# prototype2.net
KiCad netlist of a schematic drawn in EAGLE
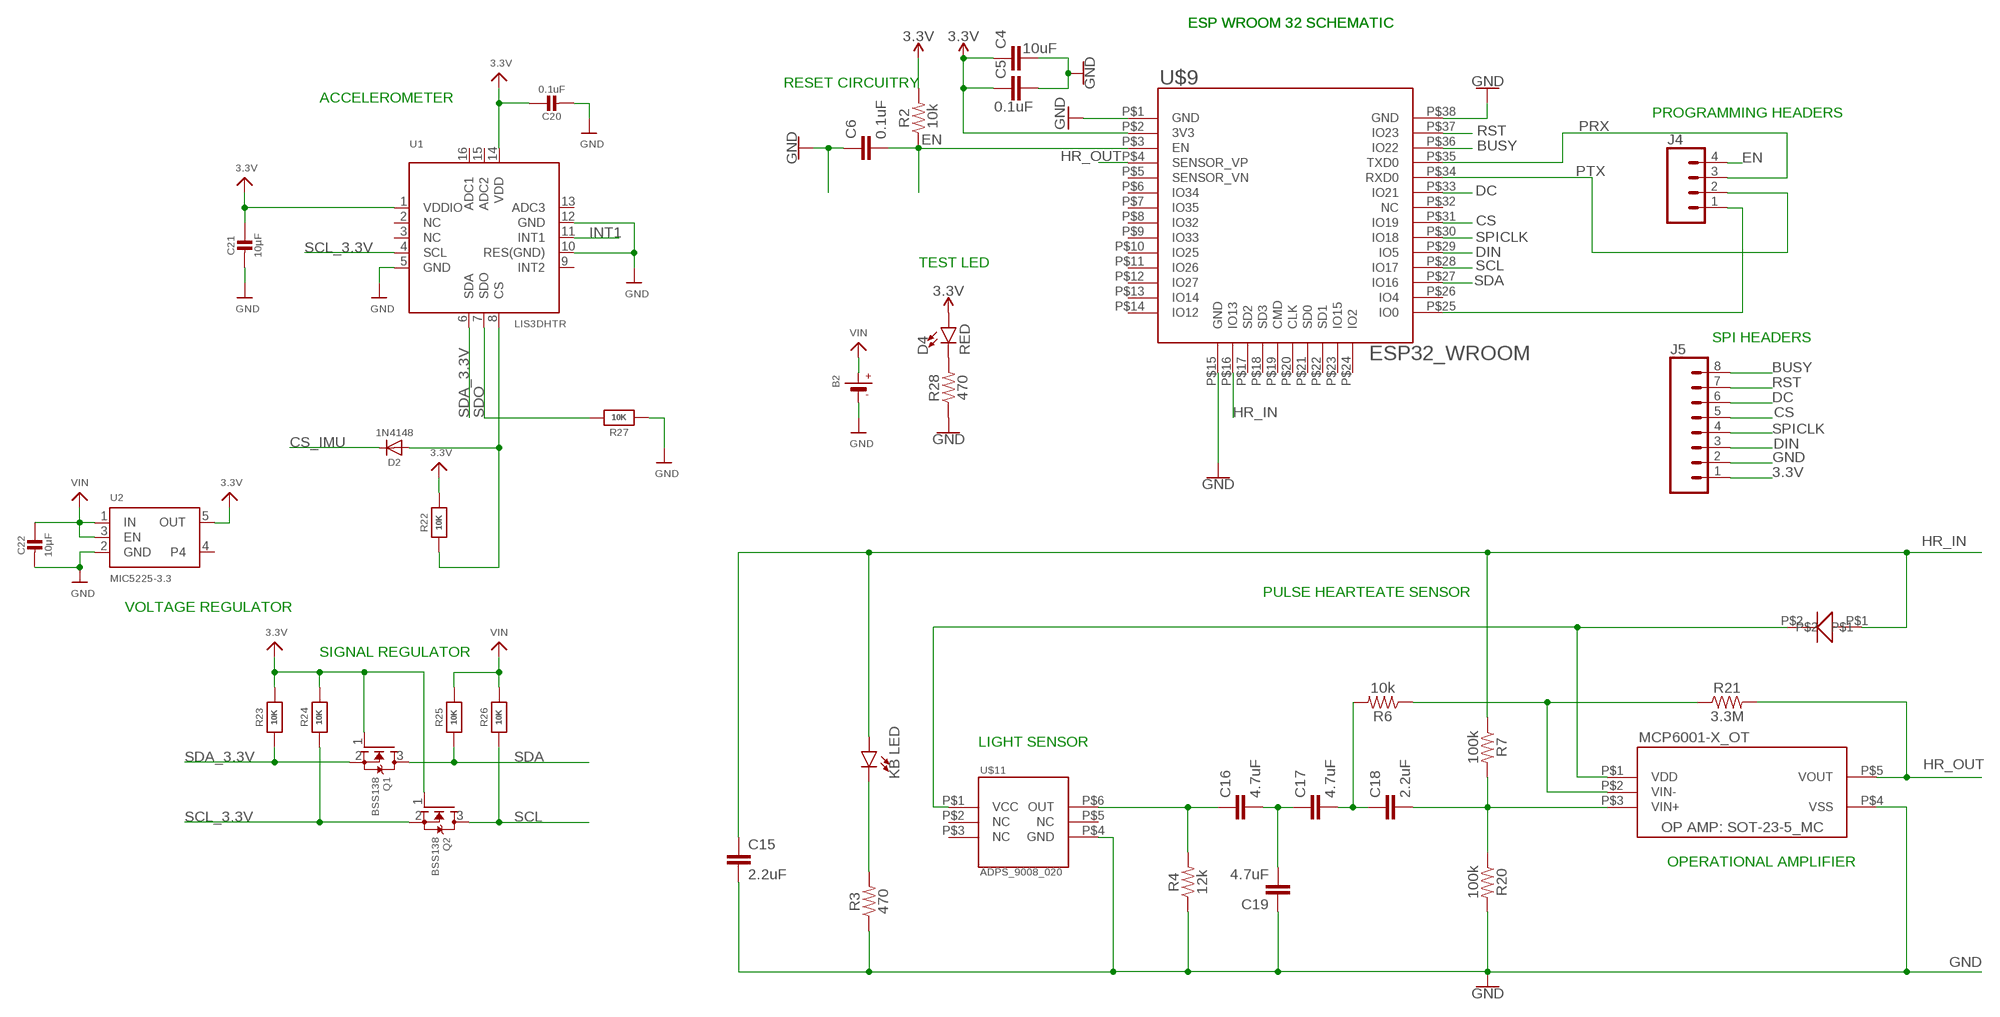
[diagram p0: schematic, sheet 1]

(export (version "E")
  (design (tool "Eeschema 10.0.6"))
  (components
    (comp (ref "B2")
      (value "BATTERYCR2032_BAT-HLD-001")
      (footprint "eagle-import:CR2032_SMT_BAT-HLD-001")
      (libsource (lib "eagle-import") (part "BATTERYCR2032_BAT-HLD-001"))
    )
    (comp (ref "C4")
      (value "10uF")
      (footprint "eagle-import:0603")
      (libsource (lib "eagle-import") (part "10UF-0603-6.3V-20%"))
    )
    (comp (ref "C5")
      (value "0.1uF")
      (footprint "eagle-import:0603")
      (libsource (lib "eagle-import") (part "0.1UF-0603-25V-(+80/-20%)"))
    )
    (comp (ref "C6")
      (value "0.1uF")
      (footprint "eagle-import:0603")
      (libsource (lib "eagle-import") (part "0.1UF-0603-25V-(+80/-20%)"))
    )
    (comp (ref "C15")
      (value "2.2uF")
      (footprint "eagle-import:0603")
      (libsource (lib "eagle-import") (part "2.2UF-0603-10V-20%"))
    )
    (comp (ref "C16")
      (value "4.7uF")
      (footprint "eagle-import:0603")
      (libsource (lib "eagle-import") (part "4.7UF0603"))
    )
    (comp (ref "C17")
      (value "4.7uF")
      (footprint "eagle-import:0603")
      (libsource (lib "eagle-import") (part "4.7UF0603"))
    )
    (comp (ref "C18")
      (value "2.2uF")
      (footprint "eagle-import:0603")
      (libsource (lib "eagle-import") (part "2.2UF-0603-10V-20%"))
    )
    (comp (ref "C19")
      (value "4.7uF")
      (footprint "eagle-import:0603")
      (libsource (lib "eagle-import") (part "4.7UF0603"))
    )
    (comp (ref "C20")
      (value "0.1uF")
      (footprint "eagle-import:_0603MP")
      (libsource (lib "eagle-import") (part "CAP_CERAMIC_0603MP"))
    )
    (comp (ref "C21")
      (value "10µF")
      (footprint "eagle-import:_0603")
      (libsource (lib "eagle-import") (part "CAP_CERAMIC_0603"))
    )
    (comp (ref "C22")
      (value "10µF")
      (footprint "eagle-import:_0603")
      (libsource (lib "eagle-import") (part "CAP_CERAMIC_0603"))
    )
    (comp (ref "D2")
      (value "1N4148")
      (footprint "eagle-import:SOD-323")
      (libsource (lib "eagle-import") (part "DIODESOD-323"))
    )
    (comp (ref "D4")
      (value "RED")
      (footprint "eagle-import:LED-0603")
      (libsource (lib "eagle-import") (part "LED-RED0603"))
    )
    (comp (ref "J4")
      (value "CONN_04")
      (footprint "eagle-import:1X04")
      (libsource (lib "eagle-import") (part "CONN_04"))
    )
    (comp (ref "J5")
      (value "CONN_08\"")
      (footprint "eagle-import:1X08")
      (libsource (lib "eagle-import") (part "CONN_08{dblquote}"))
    )
    (comp (ref "Q1")
      (value "BSS138")
      (footprint "eagle-import:SOT23-WIDE")
      (libsource (lib "eagle-import") (part "MOSFET-NWIDE"))
    )
    (comp (ref "Q2")
      (value "BSS138")
      (footprint "eagle-import:SOT23-WIDE")
      (libsource (lib "eagle-import") (part "MOSFET-NWIDE"))
    )
    (comp (ref "R2")
      (value "10k")
      (footprint "eagle-import:0603")
      (libsource (lib "eagle-import") (part "RESISTOR0603"))
    )
    (comp (ref "R3")
      (value "470")
      (footprint "eagle-import:0603")
      (libsource (lib "eagle-import") (part "RESISTOR0603"))
    )
    (comp (ref "R4")
      (value "12k")
      (footprint "eagle-import:0603")
      (libsource (lib "eagle-import") (part "RESISTOR0603"))
    )
    (comp (ref "R6")
      (value "10k")
      (footprint "eagle-import:0603")
      (libsource (lib "eagle-import") (part "RESISTOR0603"))
    )
    (comp (ref "R7")
      (value "100k")
      (footprint "eagle-import:0603")
      (libsource (lib "eagle-import") (part "RESISTOR0603"))
    )
    (comp (ref "R20")
      (value "100k")
      (footprint "eagle-import:0603")
      (libsource (lib "eagle-import") (part "RESISTOR0603"))
    )
    (comp (ref "R21")
      (value "3.3M")
      (footprint "eagle-import:0603")
      (libsource (lib "eagle-import") (part "RESISTOR0603"))
    )
    (comp (ref "R22")
      (value "10K")
      (footprint "eagle-import:_0603")
      (libsource (lib "eagle-import") (part "RESISTOR_0603"))
    )
    (comp (ref "R23")
      (value "10K")
      (footprint "eagle-import:_0603")
      (libsource (lib "eagle-import") (part "RESISTOR_0603"))
    )
    (comp (ref "R24")
      (value "10K")
      (footprint "eagle-import:_0603")
      (libsource (lib "eagle-import") (part "RESISTOR_0603"))
    )
    (comp (ref "R25")
      (value "10K")
      (footprint "eagle-import:_0603")
      (libsource (lib "eagle-import") (part "RESISTOR_0603"))
    )
    (comp (ref "R26")
      (value "10K")
      (footprint "eagle-import:_0603")
      (libsource (lib "eagle-import") (part "RESISTOR_0603"))
    )
    (comp (ref "R27")
      (value "10K")
      (footprint "eagle-import:_0603")
      (libsource (lib "eagle-import") (part "RESISTOR_0603"))
    )
    (comp (ref "R28")
      (value "470")
      (footprint "eagle-import:0603")
      (libsource (lib "eagle-import") (part "RESISTOR0603"))
    )
    (comp (ref "U$9")
      (value "ESP32_WROOM")
      (footprint "eagle-import:ESP32_FP")
      (libsource (lib "eagle-import") (part "ESP32_WROOM"))
    )
    (comp (ref "U$10")
      (value "MCP6001-X_SOT-23-5")
      (footprint "eagle-import:SOT-23-5")
      (libsource (lib "eagle-import") (part "MCP6001-X_SOT-23-5"))
    )
    (comp (ref "U$11")
      (value "ADPS_9008_020")
      (footprint "eagle-import:ADPS_FP")
      (libsource (lib "eagle-import") (part "ADPS_9008_020"))
    )
    (comp (ref "U$12")
      (value "KB_REVMNT_LED")
      (footprint "eagle-import:REVMNT_LED_FP")
      (libsource (lib "eagle-import") (part "KB_REVMNT_LED"))
    )
    (comp (ref "U$42")
      (value "DI0603")
      (footprint "eagle-import:DIODE0603")
      (libsource (lib "eagle-import") (part "DI0603"))
    )
    (comp (ref "U1")
      (value "LIS3DHTR")
      (footprint "eagle-import:LGA16_3X3MM")
      (libsource (lib "eagle-import") (part "ACCEL_LIS3DHTR"))
    )
    (comp (ref "U2")
      (value "MIC5225-3.3")
      (footprint "eagle-import:SOT23-5")
      (libsource (lib "eagle-import") (part "VREG_SOT23-5"))
    )
  )
  (nets
    (net (code "1") (name "/BUSY") (class "Default")
      (node (ref "J5") (pin "8") (pinfunction "8_8") (pintype "passive"))
      (node (ref "U$9") (pin "P$36") (pinfunction "IO22_P$36") (pintype "bidirectional"))
    )
    (net (code "2") (name "/CS") (class "Default")
      (node (ref "J5") (pin "5") (pinfunction "5_5") (pintype "passive"))
      (node (ref "U$9") (pin "P$31") (pinfunction "IO19_P$31") (pintype "bidirectional"))
    )
    (net (code "3") (name "/CS_IMU") (class "Default")
      (node (ref "D2") (pin "C") (pinfunction "C_C") (pintype "passive"))
    )
    (net (code "4") (name "/DC") (class "Default")
      (node (ref "J5") (pin "6") (pinfunction "6_6") (pintype "passive"))
      (node (ref "U$9") (pin "P$33") (pinfunction "IO21_P$33") (pintype "bidirectional"))
    )
    (net (code "5") (name "/DIN") (class "Default")
      (node (ref "J5") (pin "3") (pinfunction "3_3") (pintype "passive"))
      (node (ref "U$9") (pin "P$29") (pinfunction "IO5_P$29") (pintype "bidirectional"))
    )
    (net (code "6") (name "/EN") (class "Default")
      (node (ref "C6") (pin "2") (pinfunction "2_2") (pintype "passive"))
      (node (ref "J4") (pin "4") (pinfunction "4_4") (pintype "passive"))
      (node (ref "R2") (pin "1") (pinfunction "1_1") (pintype "passive"))
      (node (ref "U$9") (pin "P$3") (pinfunction "EN_P$3") (pintype "input"))
    )
    (net (code "7") (name "/HR_IN") (class "Default")
      (node (ref "C15") (pin "1") (pinfunction "1_1") (pintype "passive"))
      (node (ref "R7") (pin "1") (pinfunction "1_1") (pintype "passive"))
      (node (ref "U$12") (pin "P$1") (pinfunction "A_P$1") (pintype "passive"))
      (node (ref "U$42") (pin "P$1") (pinfunction "P$2_P$1") (pintype "bidirectional"))
      (node (ref "U$9") (pin "P$16") (pinfunction "IO13_P$16") (pintype "bidirectional"))
    )
    (net (code "8") (name "/HR_OUT") (class "Default")
      (node (ref "R21") (pin "2") (pinfunction "2_2") (pintype "passive"))
      (node (ref "U$10") (pin "P$5") (pinfunction "VOUT_P$5") (pintype "output"))
      (node (ref "U$9") (pin "P$4") (pinfunction "SENSOR_VP_P$4") (pintype "input"))
    )
    (net (code "9") (name "/INT1") (class "Default")
      (node (ref "U1") (pin "11") (pinfunction "INT1_11") (pintype "output"))
    )
    (net (code "10") (name "/PRX") (class "Default")
      (node (ref "J4") (pin "3") (pinfunction "3_3") (pintype "passive"))
      (node (ref "U$9") (pin "P$35") (pinfunction "TXD0_P$35") (pintype "bidirectional"))
    )
    (net (code "11") (name "/PTX") (class "Default")
      (node (ref "J4") (pin "2") (pinfunction "2_2") (pintype "passive"))
      (node (ref "U$9") (pin "P$34") (pinfunction "RXD0_P$34") (pintype "bidirectional"))
    )
    (net (code "12") (name "/RST") (class "Default")
      (node (ref "J5") (pin "7") (pinfunction "7_7") (pintype "passive"))
      (node (ref "U$9") (pin "P$37") (pinfunction "IO23_P$37") (pintype "bidirectional"))
    )
    (net (code "13") (name "/SCL") (class "Default")
      (node (ref "Q2") (pin "3") (pinfunction "D_3") (pintype "bidirectional"))
      (node (ref "R26") (pin "1") (pinfunction "1_1") (pintype "passive"))
      (node (ref "U$9") (pin "P$28") (pinfunction "IO17_P$28") (pintype "bidirectional"))
    )
    (net (code "14") (name "/SCL_3.3V") (class "Default")
      (node (ref "Q2") (pin "2") (pinfunction "S_2") (pintype "bidirectional"))
      (node (ref "R24") (pin "1") (pinfunction "1_1") (pintype "passive"))
      (node (ref "U1") (pin "4") (pinfunction "SCL_4") (pintype "bidirectional"))
    )
    (net (code "15") (name "/SDA") (class "Default")
      (node (ref "Q1") (pin "3") (pinfunction "D_3") (pintype "bidirectional"))
      (node (ref "R25") (pin "1") (pinfunction "1_1") (pintype "passive"))
      (node (ref "U$9") (pin "P$27") (pinfunction "IO16_P$27") (pintype "bidirectional"))
    )
    (net (code "16") (name "/SDA_3.3V") (class "Default")
      (node (ref "Q1") (pin "2") (pinfunction "S_2") (pintype "bidirectional"))
      (node (ref "R23") (pin "1") (pinfunction "1_1") (pintype "passive"))
      (node (ref "U1") (pin "6") (pinfunction "SDA_6") (pintype "bidirectional"))
    )
    (net (code "17") (name "/SDO") (class "Default")
      (node (ref "R27") (pin "2") (pinfunction "2_2") (pintype "passive"))
      (node (ref "U1") (pin "7") (pinfunction "SDO_7") (pintype "bidirectional"))
    )
    (net (code "18") (name "/SPICLK") (class "Default")
      (node (ref "J5") (pin "4") (pinfunction "4_4") (pintype "passive"))
      (node (ref "U$9") (pin "P$30") (pinfunction "IO18_P$30") (pintype "bidirectional"))
    )
    (net (code "19") (name "3.3V") (class "Default")
      (node (ref "C20") (pin "1") (pinfunction "1_1") (pintype "passive"))
      (node (ref "C21") (pin "1") (pinfunction "1_1") (pintype "passive"))
      (node (ref "C4") (pin "1") (pinfunction "1_1") (pintype "passive"))
      (node (ref "C5") (pin "1") (pinfunction "1_1") (pintype "passive"))
      (node (ref "D4") (pin "A") (pinfunction "A_A") (pintype "passive"))
      (node (ref "J5") (pin "1") (pinfunction "1_1") (pintype "passive"))
      (node (ref "Q1") (pin "1") (pinfunction "G_1") (pintype "bidirectional"))
      (node (ref "Q2") (pin "1") (pinfunction "G_1") (pintype "bidirectional"))
      (node (ref "R2") (pin "2") (pinfunction "2_2") (pintype "passive"))
      (node (ref "R22") (pin "2") (pinfunction "2_2") (pintype "passive"))
      (node (ref "R23") (pin "2") (pinfunction "2_2") (pintype "passive"))
      (node (ref "R24") (pin "2") (pinfunction "2_2") (pintype "passive"))
      (node (ref "U$9") (pin "P$2") (pinfunction "3V3_P$2") (pintype "power_in"))
      (node (ref "U1") (pin "1") (pinfunction "VDDIO_1") (pintype "power_in"))
      (node (ref "U1") (pin "14") (pinfunction "VDD_14") (pintype "power_in"))
      (node (ref "U2") (pin "5") (pinfunction "OUT_5") (pintype "power_in"))
    )
    (net (code "20") (name "GND") (class "Default")
      (node (ref "B2") (pin "-") (pinfunction "-_-") (pintype "passive"))
      (node (ref "C15") (pin "2") (pinfunction "2_2") (pintype "passive"))
      (node (ref "C19") (pin "1") (pinfunction "1_1") (pintype "passive"))
      (node (ref "C20") (pin "2") (pinfunction "2_2") (pintype "passive"))
      (node (ref "C21") (pin "2") (pinfunction "2_2") (pintype "passive"))
      (node (ref "C22") (pin "2") (pinfunction "2_2") (pintype "passive"))
      (node (ref "C4") (pin "2") (pinfunction "2_2") (pintype "passive"))
      (node (ref "C5") (pin "2") (pinfunction "2_2") (pintype "passive"))
      (node (ref "C6") (pin "1") (pinfunction "1_1") (pintype "passive"))
      (node (ref "J5") (pin "2") (pinfunction "2_2") (pintype "passive"))
      (node (ref "R20") (pin "2") (pinfunction "2_2") (pintype "passive"))
      (node (ref "R27") (pin "1") (pinfunction "1_1") (pintype "passive"))
      (node (ref "R28") (pin "1") (pinfunction "1_1") (pintype "passive"))
      (node (ref "R3") (pin "1") (pinfunction "1_1") (pintype "passive"))
      (node (ref "R4") (pin "1") (pinfunction "1_1") (pintype "passive"))
      (node (ref "U$10") (pin "P$4") (pinfunction "VSS_P$4") (pintype "power_in"))
      (node (ref "U$11") (pin "P$4") (pinfunction "GND_P$4") (pintype "power_in"))
      (node (ref "U$9") (pin "P$1") (pinfunction "GND_P$1") (pintype "power_in"))
      (node (ref "U$9") (pin "P$15") (pinfunction "GND_P$15") (pintype "power_in"))
      (node (ref "U$9") (pin "P$38") (pinfunction "GND_P$38") (pintype "power_in"))
      (node (ref "U1") (pin "10") (pinfunction "RES(GND)_10") (pintype "bidirectional"))
      (node (ref "U1") (pin "12") (pinfunction "GND_12") (pintype "power_in"))
      (node (ref "U1") (pin "5") (pinfunction "GND_5") (pintype "power_in"))
      (node (ref "U2") (pin "2") (pinfunction "GND_2") (pintype "power_in"))
    )
    (net (code "21") (name "Net-(C16-Pad2)") (class "Default")
      (node (ref "C16") (pin "2") (pinfunction "2_2") (pintype "passive"))
      (node (ref "C17") (pin "1") (pinfunction "1_1") (pintype "passive"))
      (node (ref "C19") (pin "2") (pinfunction "2_2") (pintype "passive"))
    )
    (net (code "22") (name "Net-(C17-Pad2)") (class "Default")
      (node (ref "C17") (pin "2") (pinfunction "2_2") (pintype "passive"))
      (node (ref "C18") (pin "1") (pinfunction "1_1") (pintype "passive"))
      (node (ref "R6") (pin "2") (pinfunction "2_2") (pintype "passive"))
    )
    (net (code "23") (name "Net-(D4-PadC)") (class "Default")
      (node (ref "D4") (pin "C") (pinfunction "C_C") (pintype "passive"))
      (node (ref "R28") (pin "2") (pinfunction "2_2") (pintype "passive"))
    )
    (net (code "24") (name "Net-(U$9-IO0)") (class "Default")
      (node (ref "J4") (pin "1") (pinfunction "1_1") (pintype "passive"))
      (node (ref "U$9") (pin "P$25") (pinfunction "IO0_P$25") (pintype "bidirectional"))
    )
    (net (code "25") (name "Net-(U$10-VDD)") (class "Default")
      (node (ref "U$10") (pin "P$1") (pinfunction "VDD_P$1") (pintype "power_in"))
      (node (ref "U$11") (pin "P$1") (pinfunction "VCC_P$1") (pintype "power_in"))
      (node (ref "U$42") (pin "P$2") (pinfunction "P$1_P$2") (pintype "bidirectional"))
    )
    (net (code "26") (name "Net-(U$10-VIN+)") (class "Default")
      (node (ref "C18") (pin "2") (pinfunction "2_2") (pintype "passive"))
      (node (ref "R20") (pin "1") (pinfunction "1_1") (pintype "passive"))
      (node (ref "R7") (pin "2") (pinfunction "2_2") (pintype "passive"))
      (node (ref "U$10") (pin "P$3") (pinfunction "VIN+_P$3") (pintype "input"))
    )
    (net (code "27") (name "Net-(U$10-VIN-)") (class "Default")
      (node (ref "R21") (pin "1") (pinfunction "1_1") (pintype "passive"))
      (node (ref "R6") (pin "1") (pinfunction "1_1") (pintype "passive"))
      (node (ref "U$10") (pin "P$2") (pinfunction "VIN-_P$2") (pintype "input"))
    )
    (net (code "28") (name "Net-(U$11-OUT)") (class "Default")
      (node (ref "C16") (pin "1") (pinfunction "1_1") (pintype "passive"))
      (node (ref "R4") (pin "2") (pinfunction "2_2") (pintype "passive"))
      (node (ref "U$11") (pin "P$6") (pinfunction "OUT_P$6") (pintype "output"))
    )
    (net (code "29") (name "Net-(U$12-C)") (class "Default")
      (node (ref "R3") (pin "2") (pinfunction "2_2") (pintype "passive"))
      (node (ref "U$12") (pin "P$2") (pinfunction "C_P$2") (pintype "passive"))
    )
    (net (code "30") (name "Net-(U1-CS)") (class "Default")
      (node (ref "D2") (pin "A") (pinfunction "A_A") (pintype "passive"))
      (node (ref "R22") (pin "1") (pinfunction "1_1") (pintype "passive"))
      (node (ref "U1") (pin "8") (pinfunction "CS_8") (pintype "input"))
    )
    (net (code "31") (name "VIN") (class "Default")
      (node (ref "B2") (pin "+$1") (pinfunction "+_+$1") (pintype "passive"))
      (node (ref "B2") (pin "+$2") (pinfunction "+_+$2") (pintype "passive"))
      (node (ref "C22") (pin "1") (pinfunction "1_1") (pintype "passive"))
      (node (ref "R25") (pin "2") (pinfunction "2_2") (pintype "passive"))
      (node (ref "R26") (pin "2") (pinfunction "2_2") (pintype "passive"))
      (node (ref "U2") (pin "1") (pinfunction "IN_1") (pintype "power_in"))
      (node (ref "U2") (pin "3") (pinfunction "EN_3") (pintype "input"))
    )
    (net (code "32") (name "unconnected-(U$9-CLK-PadP$20)") (class "Default")
      (node (ref "U$9") (pin "P$20") (pinfunction "CLK_P$20") (pintype "bidirectional"))
    )
    (net (code "33") (name "unconnected-(U$9-CMD-PadP$19)") (class "Default")
      (node (ref "U$9") (pin "P$19") (pinfunction "CMD_P$19") (pintype "bidirectional"))
    )
    (net (code "34") (name "unconnected-(U$9-IO2-PadP$24)") (class "Default")
      (node (ref "U$9") (pin "P$24") (pinfunction "IO2_P$24") (pintype "bidirectional"))
    )
    (net (code "35") (name "unconnected-(U$9-IO4-PadP$26)") (class "Default")
      (node (ref "U$9") (pin "P$26") (pinfunction "IO4_P$26") (pintype "bidirectional"))
    )
    (net (code "36") (name "unconnected-(U$9-IO12-PadP$14)") (class "Default")
      (node (ref "U$9") (pin "P$14") (pinfunction "IO12_P$14") (pintype "bidirectional"))
    )
    (net (code "37") (name "unconnected-(U$9-IO14-PadP$13)") (class "Default")
      (node (ref "U$9") (pin "P$13") (pinfunction "IO14_P$13") (pintype "bidirectional"))
    )
    (net (code "38") (name "unconnected-(U$9-IO15-PadP$23)") (class "Default")
      (node (ref "U$9") (pin "P$23") (pinfunction "IO15_P$23") (pintype "bidirectional"))
    )
    (net (code "39") (name "unconnected-(U$9-IO25-PadP$10)") (class "Default")
      (node (ref "U$9") (pin "P$10") (pinfunction "IO25_P$10") (pintype "bidirectional"))
    )
    (net (code "40") (name "unconnected-(U$9-IO26-PadP$11)") (class "Default")
      (node (ref "U$9") (pin "P$11") (pinfunction "IO26_P$11") (pintype "bidirectional"))
    )
    (net (code "41") (name "unconnected-(U$9-IO27-PadP$12)") (class "Default")
      (node (ref "U$9") (pin "P$12") (pinfunction "IO27_P$12") (pintype "bidirectional"))
    )
    (net (code "42") (name "unconnected-(U$9-IO32-PadP$8)") (class "Default")
      (node (ref "U$9") (pin "P$8") (pinfunction "IO32_P$8") (pintype "bidirectional"))
    )
    (net (code "43") (name "unconnected-(U$9-IO33-PadP$9)") (class "Default")
      (node (ref "U$9") (pin "P$9") (pinfunction "IO33_P$9") (pintype "bidirectional"))
    )
    (net (code "44") (name "unconnected-(U$9-IO34-PadP$6)") (class "Default")
      (node (ref "U$9") (pin "P$6") (pinfunction "IO34_P$6") (pintype "bidirectional"))
    )
    (net (code "45") (name "unconnected-(U$9-IO35-PadP$7)") (class "Default")
      (node (ref "U$9") (pin "P$7") (pinfunction "IO35_P$7") (pintype "bidirectional"))
    )
    (net (code "46") (name "unconnected-(U$9-NC-PadP$32)") (class "Default")
      (node (ref "U$9") (pin "P$32") (pinfunction "NC_P$32") (pintype "no_connect"))
    )
    (net (code "47") (name "unconnected-(U$9-SD0-PadP$21)") (class "Default")
      (node (ref "U$9") (pin "P$21") (pinfunction "SD0_P$21") (pintype "bidirectional"))
    )
    (net (code "48") (name "unconnected-(U$9-SD1-PadP$22)") (class "Default")
      (node (ref "U$9") (pin "P$22") (pinfunction "SD1_P$22") (pintype "bidirectional"))
    )
    (net (code "49") (name "unconnected-(U$9-SD2-PadP$17)") (class "Default")
      (node (ref "U$9") (pin "P$17") (pinfunction "SD2_P$17") (pintype "bidirectional"))
    )
    (net (code "50") (name "unconnected-(U$9-SD3-PadP$18)") (class "Default")
      (node (ref "U$9") (pin "P$18") (pinfunction "SD3_P$18") (pintype "bidirectional"))
    )
    (net (code "51") (name "unconnected-(U$9-SENSOR_VN-PadP$5)") (class "Default")
      (node (ref "U$9") (pin "P$5") (pinfunction "SENSOR_VN_P$5") (pintype "input"))
    )
    (net (code "52") (name "unconnected-(U$11-NC-PadP$2)") (class "Default")
      (node (ref "U$11") (pin "P$2") (pinfunction "NC_P$2") (pintype "bidirectional"))
    )
    (net (code "53") (name "unconnected-(U$11-NC-PadP$3)") (class "Default")
      (node (ref "U$11") (pin "P$3") (pinfunction "NC_P$3") (pintype "bidirectional"))
    )
    (net (code "54") (name "unconnected-(U$11-NC-PadP$5)") (class "Default")
      (node (ref "U$11") (pin "P$5") (pinfunction "NC_P$5") (pintype "bidirectional"))
    )
    (net (code "55") (name "unconnected-(U1-ADC1-Pad16)") (class "Default")
      (node (ref "U1") (pin "16") (pinfunction "ADC1_16") (pintype "input"))
    )
    (net (code "56") (name "unconnected-(U1-ADC2-Pad15)") (class "Default")
      (node (ref "U1") (pin "15") (pinfunction "ADC2_15") (pintype "input"))
    )
    (net (code "57") (name "unconnected-(U1-ADC3-Pad13)") (class "Default")
      (node (ref "U1") (pin "13") (pinfunction "ADC3_13") (pintype "input"))
    )
    (net (code "58") (name "unconnected-(U1-INT2-Pad9)") (class "Default")
      (node (ref "U1") (pin "9") (pinfunction "INT2_9") (pintype "output"))
    )
    (net (code "59") (name "unconnected-(U1-NC-Pad2)") (class "Default")
      (node (ref "U1") (pin "2") (pinfunction "NC_2") (pintype "no_connect"))
    )
    (net (code "60") (name "unconnected-(U1-NC-Pad3)") (class "Default")
      (node (ref "U1") (pin "3") (pinfunction "NC_3") (pintype "no_connect"))
    )
    (net (code "61") (name "unconnected-(U2-P4-Pad4)") (class "Default")
      (node (ref "U2") (pin "4") (pinfunction "P4_4") (pintype "bidirectional"))
    )
  )
)
